# pantalla.net
KiCad netlist of a schematic drawn in EAGLE
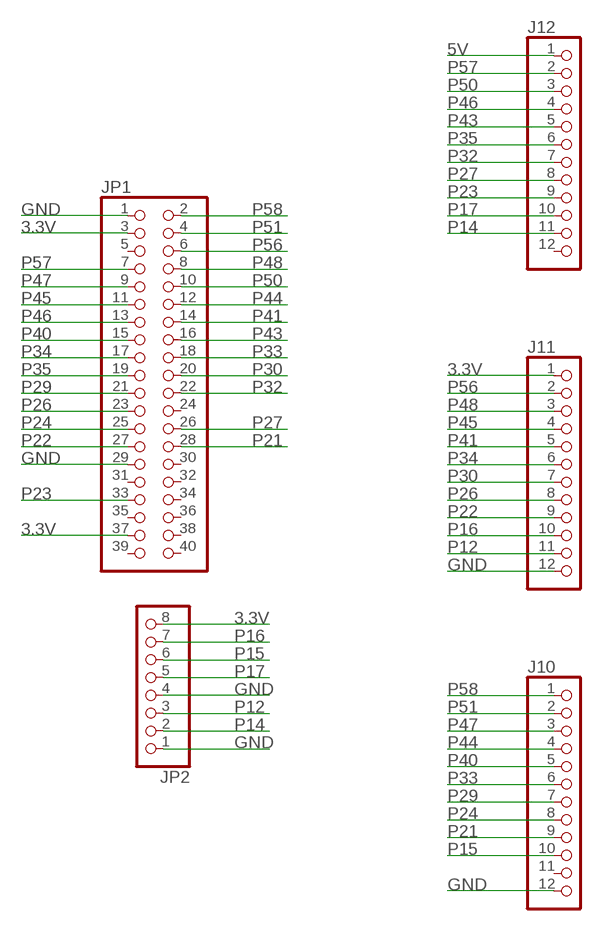
[diagram p0: schematic, sheet 1]

(export (version "E")
  (design (tool "Eeschema 10.0.6"))
  (components
    (comp (ref "J10")
      (value "PINHD-1X12")
      (footprint "eagle-import:1X12")
      (libsource (lib "eagle-import") (part "PINHD-1X12"))
    )
    (comp (ref "J11")
      (value "PINHD-1X12")
      (footprint "eagle-import:1X12")
      (libsource (lib "eagle-import") (part "PINHD-1X12"))
    )
    (comp (ref "J12")
      (value "PINHD-1X12")
      (footprint "eagle-import:1X12")
      (libsource (lib "eagle-import") (part "PINHD-1X12"))
    )
    (comp (ref "JP1")
      (value "PINHD-2X20")
      (footprint "eagle-import:2X20")
      (libsource (lib "eagle-import") (part "PINHD-2X20"))
    )
    (comp (ref "JP2")
      (value "PINHD-1X8")
      (footprint "eagle-import:1X08")
      (libsource (lib "eagle-import") (part "PINHD-1X8"))
    )
  )
  (nets
    (net (code "1") (name "/3.3V") (class "Default")
      (node (ref "J11") (pin "1") (pinfunction "1_1") (pintype "passive"))
      (node (ref "JP1") (pin "3") (pinfunction "3_3") (pintype "passive"))
      (node (ref "JP1") (pin "37") (pinfunction "37_37") (pintype "passive"))
      (node (ref "JP2") (pin "8") (pinfunction "8_8") (pintype "passive"))
    )
    (net (code "2") (name "/5V") (class "Default")
      (node (ref "J12") (pin "1") (pinfunction "1_1") (pintype "passive"))
    )
    (net (code "3") (name "/GND") (class "Default")
      (node (ref "J10") (pin "12") (pinfunction "12_12") (pintype "passive"))
      (node (ref "J11") (pin "12") (pinfunction "12_12") (pintype "passive"))
      (node (ref "JP1") (pin "1") (pinfunction "1_1") (pintype "passive"))
      (node (ref "JP1") (pin "29") (pinfunction "29_29") (pintype "passive"))
      (node (ref "JP2") (pin "1") (pinfunction "1_1") (pintype "passive"))
      (node (ref "JP2") (pin "4") (pinfunction "4_4") (pintype "passive"))
    )
    (net (code "4") (name "/P12") (class "Default")
      (node (ref "J11") (pin "11") (pinfunction "11_11") (pintype "passive"))
      (node (ref "JP2") (pin "3") (pinfunction "3_3") (pintype "passive"))
    )
    (net (code "5") (name "/P14") (class "Default")
      (node (ref "J12") (pin "11") (pinfunction "11_11") (pintype "passive"))
      (node (ref "JP2") (pin "2") (pinfunction "2_2") (pintype "passive"))
    )
    (net (code "6") (name "/P15") (class "Default")
      (node (ref "J10") (pin "10") (pinfunction "10_10") (pintype "passive"))
      (node (ref "JP2") (pin "6") (pinfunction "6_6") (pintype "passive"))
    )
    (net (code "7") (name "/P16") (class "Default")
      (node (ref "J11") (pin "10") (pinfunction "10_10") (pintype "passive"))
      (node (ref "JP2") (pin "7") (pinfunction "7_7") (pintype "passive"))
    )
    (net (code "8") (name "/P17") (class "Default")
      (node (ref "J12") (pin "10") (pinfunction "10_10") (pintype "passive"))
      (node (ref "JP2") (pin "5") (pinfunction "5_5") (pintype "passive"))
    )
    (net (code "9") (name "/P21") (class "Default")
      (node (ref "J10") (pin "9") (pinfunction "9_9") (pintype "passive"))
      (node (ref "JP1") (pin "28") (pinfunction "28_28") (pintype "passive"))
    )
    (net (code "10") (name "/P22") (class "Default")
      (node (ref "J11") (pin "9") (pinfunction "9_9") (pintype "passive"))
      (node (ref "JP1") (pin "27") (pinfunction "27_27") (pintype "passive"))
    )
    (net (code "11") (name "/P23") (class "Default")
      (node (ref "J12") (pin "9") (pinfunction "9_9") (pintype "passive"))
      (node (ref "JP1") (pin "33") (pinfunction "33_33") (pintype "passive"))
    )
    (net (code "12") (name "/P24") (class "Default")
      (node (ref "J10") (pin "8") (pinfunction "8_8") (pintype "passive"))
      (node (ref "JP1") (pin "25") (pinfunction "25_25") (pintype "passive"))
    )
    (net (code "13") (name "/P26") (class "Default")
      (node (ref "J11") (pin "8") (pinfunction "8_8") (pintype "passive"))
      (node (ref "JP1") (pin "23") (pinfunction "23_23") (pintype "passive"))
    )
    (net (code "14") (name "/P27") (class "Default")
      (node (ref "J12") (pin "8") (pinfunction "8_8") (pintype "passive"))
      (node (ref "JP1") (pin "26") (pinfunction "26_26") (pintype "passive"))
    )
    (net (code "15") (name "/P29") (class "Default")
      (node (ref "J10") (pin "7") (pinfunction "7_7") (pintype "passive"))
      (node (ref "JP1") (pin "21") (pinfunction "21_21") (pintype "passive"))
    )
    (net (code "16") (name "/P30") (class "Default")
      (node (ref "J11") (pin "7") (pinfunction "7_7") (pintype "passive"))
      (node (ref "JP1") (pin "20") (pinfunction "20_20") (pintype "passive"))
    )
    (net (code "17") (name "/P32") (class "Default")
      (node (ref "J12") (pin "7") (pinfunction "7_7") (pintype "passive"))
      (node (ref "JP1") (pin "22") (pinfunction "22_22") (pintype "passive"))
    )
    (net (code "18") (name "/P33") (class "Default")
      (node (ref "J10") (pin "6") (pinfunction "6_6") (pintype "passive"))
      (node (ref "JP1") (pin "18") (pinfunction "18_18") (pintype "passive"))
    )
    (net (code "19") (name "/P34") (class "Default")
      (node (ref "J11") (pin "6") (pinfunction "6_6") (pintype "passive"))
      (node (ref "JP1") (pin "17") (pinfunction "17_17") (pintype "passive"))
    )
    (net (code "20") (name "/P35") (class "Default")
      (node (ref "J12") (pin "6") (pinfunction "6_6") (pintype "passive"))
      (node (ref "JP1") (pin "19") (pinfunction "19_19") (pintype "passive"))
    )
    (net (code "21") (name "/P40") (class "Default")
      (node (ref "J10") (pin "5") (pinfunction "5_5") (pintype "passive"))
      (node (ref "JP1") (pin "15") (pinfunction "15_15") (pintype "passive"))
    )
    (net (code "22") (name "/P41") (class "Default")
      (node (ref "J11") (pin "5") (pinfunction "5_5") (pintype "passive"))
      (node (ref "JP1") (pin "14") (pinfunction "14_14") (pintype "passive"))
    )
    (net (code "23") (name "/P43") (class "Default")
      (node (ref "J12") (pin "5") (pinfunction "5_5") (pintype "passive"))
      (node (ref "JP1") (pin "16") (pinfunction "16_16") (pintype "passive"))
    )
    (net (code "24") (name "/P44") (class "Default")
      (node (ref "J10") (pin "4") (pinfunction "4_4") (pintype "passive"))
      (node (ref "JP1") (pin "12") (pinfunction "12_12") (pintype "passive"))
    )
    (net (code "25") (name "/P45") (class "Default")
      (node (ref "J11") (pin "4") (pinfunction "4_4") (pintype "passive"))
      (node (ref "JP1") (pin "11") (pinfunction "11_11") (pintype "passive"))
    )
    (net (code "26") (name "/P46") (class "Default")
      (node (ref "J12") (pin "4") (pinfunction "4_4") (pintype "passive"))
      (node (ref "JP1") (pin "13") (pinfunction "13_13") (pintype "passive"))
    )
    (net (code "27") (name "/P47") (class "Default")
      (node (ref "J10") (pin "3") (pinfunction "3_3") (pintype "passive"))
      (node (ref "JP1") (pin "9") (pinfunction "9_9") (pintype "passive"))
    )
    (net (code "28") (name "/P48") (class "Default")
      (node (ref "J11") (pin "3") (pinfunction "3_3") (pintype "passive"))
      (node (ref "JP1") (pin "8") (pinfunction "8_8") (pintype "passive"))
    )
    (net (code "29") (name "/P50") (class "Default")
      (node (ref "J12") (pin "3") (pinfunction "3_3") (pintype "passive"))
      (node (ref "JP1") (pin "10") (pinfunction "10_10") (pintype "passive"))
    )
    (net (code "30") (name "/P51") (class "Default")
      (node (ref "J10") (pin "2") (pinfunction "2_2") (pintype "passive"))
      (node (ref "JP1") (pin "4") (pinfunction "4_4") (pintype "passive"))
    )
    (net (code "31") (name "/P56") (class "Default")
      (node (ref "J11") (pin "2") (pinfunction "2_2") (pintype "passive"))
      (node (ref "JP1") (pin "6") (pinfunction "6_6") (pintype "passive"))
    )
    (net (code "32") (name "/P57") (class "Default")
      (node (ref "J12") (pin "2") (pinfunction "2_2") (pintype "passive"))
      (node (ref "JP1") (pin "7") (pinfunction "7_7") (pintype "passive"))
    )
    (net (code "33") (name "/P58") (class "Default")
      (node (ref "J10") (pin "1") (pinfunction "1_1") (pintype "passive"))
      (node (ref "JP1") (pin "2") (pinfunction "2_2") (pintype "passive"))
    )
    (net (code "34") (name "unconnected-(J10-Pad11)") (class "Default")
      (node (ref "J10") (pin "11") (pinfunction "11_11") (pintype "passive"))
    )
    (net (code "35") (name "unconnected-(J12-Pad12)") (class "Default")
      (node (ref "J12") (pin "12") (pinfunction "12_12") (pintype "passive"))
    )
    (net (code "36") (name "unconnected-(JP1-Pad5)") (class "Default")
      (node (ref "JP1") (pin "5") (pinfunction "5_5") (pintype "passive"))
    )
    (net (code "37") (name "unconnected-(JP1-Pad24)") (class "Default")
      (node (ref "JP1") (pin "24") (pinfunction "24_24") (pintype "passive"))
    )
    (net (code "38") (name "unconnected-(JP1-Pad30)") (class "Default")
      (node (ref "JP1") (pin "30") (pinfunction "30_30") (pintype "passive"))
    )
    (net (code "39") (name "unconnected-(JP1-Pad31)") (class "Default")
      (node (ref "JP1") (pin "31") (pinfunction "31_31") (pintype "passive"))
    )
    (net (code "40") (name "unconnected-(JP1-Pad32)") (class "Default")
      (node (ref "JP1") (pin "32") (pinfunction "32_32") (pintype "passive"))
    )
    (net (code "41") (name "unconnected-(JP1-Pad34)") (class "Default")
      (node (ref "JP1") (pin "34") (pinfunction "34_34") (pintype "passive"))
    )
    (net (code "42") (name "unconnected-(JP1-Pad35)") (class "Default")
      (node (ref "JP1") (pin "35") (pinfunction "35_35") (pintype "passive"))
    )
    (net (code "43") (name "unconnected-(JP1-Pad36)") (class "Default")
      (node (ref "JP1") (pin "36") (pinfunction "36_36") (pintype "passive"))
    )
    (net (code "44") (name "unconnected-(JP1-Pad38)") (class "Default")
      (node (ref "JP1") (pin "38") (pinfunction "38_38") (pintype "passive"))
    )
    (net (code "45") (name "unconnected-(JP1-Pad39)") (class "Default")
      (node (ref "JP1") (pin "39") (pinfunction "39_39") (pintype "passive"))
    )
    (net (code "46") (name "unconnected-(JP1-Pad40)") (class "Default")
      (node (ref "JP1") (pin "40") (pinfunction "40_40") (pintype "passive"))
    )
  )
)
